# tinyisp-v0_9.net
KiCad netlist of a schematic drawn in EAGLE
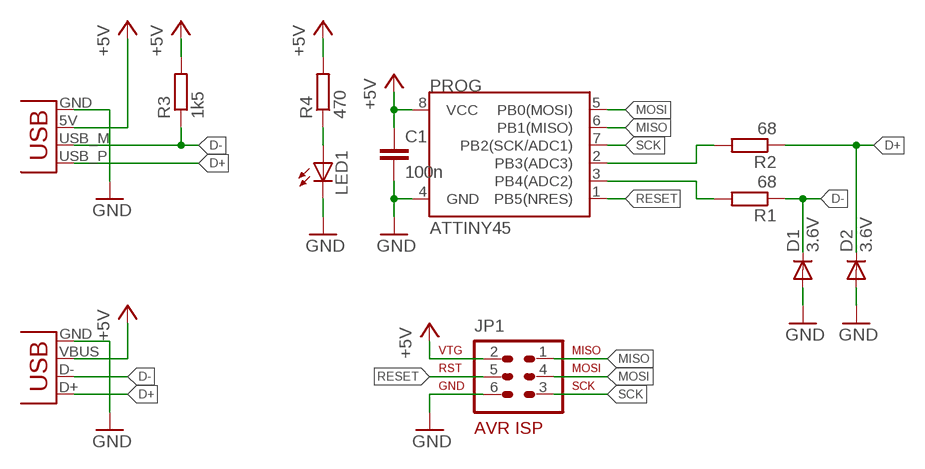
[diagram p0: schematic, sheet 1]

(export (version "E")
  (design (tool "Eeschema 10.0.6"))
  (components
    (comp (ref "C1")
      (value "100n")
      (footprint "eagle-import:C0805")
      (libsource (lib "eagle-import") (part "C-EUC0805"))
    )
    (comp (ref "D1")
      (value "3.6V")
      (footprint "eagle-import:MINIMELF")
      (libsource (lib "eagle-import") (part "DIODE-MINIMELF"))
    )
    (comp (ref "D2")
      (value "3.6V")
      (footprint "eagle-import:MINIMELF")
      (libsource (lib "eagle-import") (part "DIODE-MINIMELF"))
    )
    (comp (ref "JP1")
      (value "AVR-ISP-6")
      (footprint "eagle-import:AVR-ISP-6")
      (libsource (lib "eagle-import") (part "AVR-ISP-6"))
    )
    (comp (ref "LED1")
      (value "LEDCHIP-LED0805")
      (footprint "eagle-import:CHIP-LED0805")
      (libsource (lib "eagle-import") (part "LEDCHIP-LED0805"))
    )
    (comp (ref "PROG")
      (value "ATTINY45")
      (footprint "eagle-import:SO08-EIAJ")
      (libsource (lib "eagle-import") (part "ATTINY45"))
    )
    (comp (ref "R1")
      (value "68")
      (footprint "eagle-import:R0805")
      (libsource (lib "eagle-import") (part "R-EU_R0805"))
    )
    (comp (ref "R2")
      (value "68")
      (footprint "eagle-import:R0805")
      (libsource (lib "eagle-import") (part "R-EU_R0805"))
    )
    (comp (ref "R3")
      (value "1k5")
      (footprint "eagle-import:R0805")
      (libsource (lib "eagle-import") (part "R-EU_R0805"))
    )
    (comp (ref "R4")
      (value "470")
      (footprint "eagle-import:R0805")
      (libsource (lib "eagle-import") (part "R-EU_R0805"))
    )
    (comp (ref "X1")
      (value "USBPCB")
      (footprint "eagle-import:USB-A-PCB")
      (libsource (lib "eagle-import") (part "USBPCB"))
    )
    (comp (ref "X2")
      (value "USBMINI_B_NOHOLES")
      (footprint "eagle-import:USB_MINI_B_NOHOLES")
      (libsource (lib "eagle-import") (part "USBMINI_B_NOHOLES"))
    )
  )
  (nets
    (net (code "1") (name "+5V") (class "Default")
      (node (ref "C1") (pin "1") (pinfunction "1_1") (pintype "passive"))
      (node (ref "JP1") (pin "2") (pinfunction "2_2") (pintype "passive"))
      (node (ref "PROG") (pin "8") (pinfunction "VCC_8") (pintype "bidirectional"))
      (node (ref "R3") (pin "2") (pinfunction "2_2") (pintype "passive"))
      (node (ref "R4") (pin "2") (pinfunction "2_2") (pintype "passive"))
      (node (ref "X1") (pin "5V") (pinfunction "VBUS_5V") (pintype "bidirectional"))
      (node (ref "X2") (pin "VBUS") (pinfunction "VBUS_VBUS") (pintype "bidirectional"))
    )
    (net (code "2") (name "D+") (class "Default")
      (node (ref "D2") (pin "C") (pinfunction "C_C") (pintype "passive"))
      (node (ref "R2") (pin "1") (pinfunction "1_1") (pintype "passive"))
      (node (ref "X1") (pin "USB_P") (pinfunction "D+_USB_P") (pintype "bidirectional"))
      (node (ref "X2") (pin "D+") (pinfunction "D+_D+") (pintype "bidirectional"))
    )
    (net (code "3") (name "D-") (class "Default")
      (node (ref "D1") (pin "C") (pinfunction "C_C") (pintype "passive"))
      (node (ref "R1") (pin "1") (pinfunction "1_1") (pintype "passive"))
      (node (ref "R3") (pin "1") (pinfunction "1_1") (pintype "passive"))
      (node (ref "X1") (pin "USB_M") (pinfunction "D-_USB_M") (pintype "bidirectional"))
      (node (ref "X2") (pin "D-") (pinfunction "D-_D-") (pintype "bidirectional"))
    )
    (net (code "4") (name "GND") (class "Default")
      (node (ref "C1") (pin "2") (pinfunction "2_2") (pintype "passive"))
      (node (ref "D1") (pin "A") (pinfunction "A_A") (pintype "passive"))
      (node (ref "D2") (pin "A") (pinfunction "A_A") (pintype "passive"))
      (node (ref "JP1") (pin "6") (pinfunction "6_6") (pintype "passive"))
      (node (ref "LED1") (pin "C") (pinfunction "C_C") (pintype "passive"))
      (node (ref "PROG") (pin "4") (pinfunction "GND_4") (pintype "bidirectional"))
      (node (ref "X1") (pin "GND") (pinfunction "GND_GND") (pintype "bidirectional"))
      (node (ref "X2") (pin "GND") (pinfunction "GND_GND") (pintype "bidirectional"))
    )
    (net (code "5") (name "MISO") (class "Default")
      (node (ref "JP1") (pin "1") (pinfunction "1_1") (pintype "passive"))
      (node (ref "PROG") (pin "6") (pinfunction "PB1(MISO)_6") (pintype "bidirectional"))
    )
    (net (code "6") (name "MOSI") (class "Default")
      (node (ref "JP1") (pin "4") (pinfunction "4_4") (pintype "passive"))
      (node (ref "PROG") (pin "5") (pinfunction "PB0(MOSI)_5") (pintype "bidirectional"))
    )
    (net (code "7") (name "Net-(LED1-PadA)") (class "Default")
      (node (ref "LED1") (pin "A") (pinfunction "A_A") (pintype "passive"))
      (node (ref "R4") (pin "1") (pinfunction "1_1") (pintype "passive"))
    )
    (net (code "8") (name "Net-(PROG-PB3(ADC3))") (class "Default")
      (node (ref "PROG") (pin "2") (pinfunction "PB3(ADC3)_2") (pintype "bidirectional"))
      (node (ref "R2") (pin "2") (pinfunction "2_2") (pintype "passive"))
    )
    (net (code "9") (name "Net-(PROG-PB4(ADC2))") (class "Default")
      (node (ref "PROG") (pin "3") (pinfunction "PB4(ADC2)_3") (pintype "bidirectional"))
      (node (ref "R1") (pin "2") (pinfunction "2_2") (pintype "passive"))
    )
    (net (code "10") (name "RESET") (class "Default")
      (node (ref "JP1") (pin "5") (pinfunction "5_5") (pintype "passive"))
      (node (ref "PROG") (pin "1") (pinfunction "PB5(NRES)_1") (pintype "bidirectional"))
    )
    (net (code "11") (name "SCK") (class "Default")
      (node (ref "JP1") (pin "3") (pinfunction "3_3") (pintype "passive"))
      (node (ref "PROG") (pin "7") (pinfunction "PB2(SCK/ADC1)_7") (pintype "bidirectional"))
    )
  )
)
